# MainBoard_ETH_RASP.net
KiCad netlist of a schematic drawn in Altium Designer
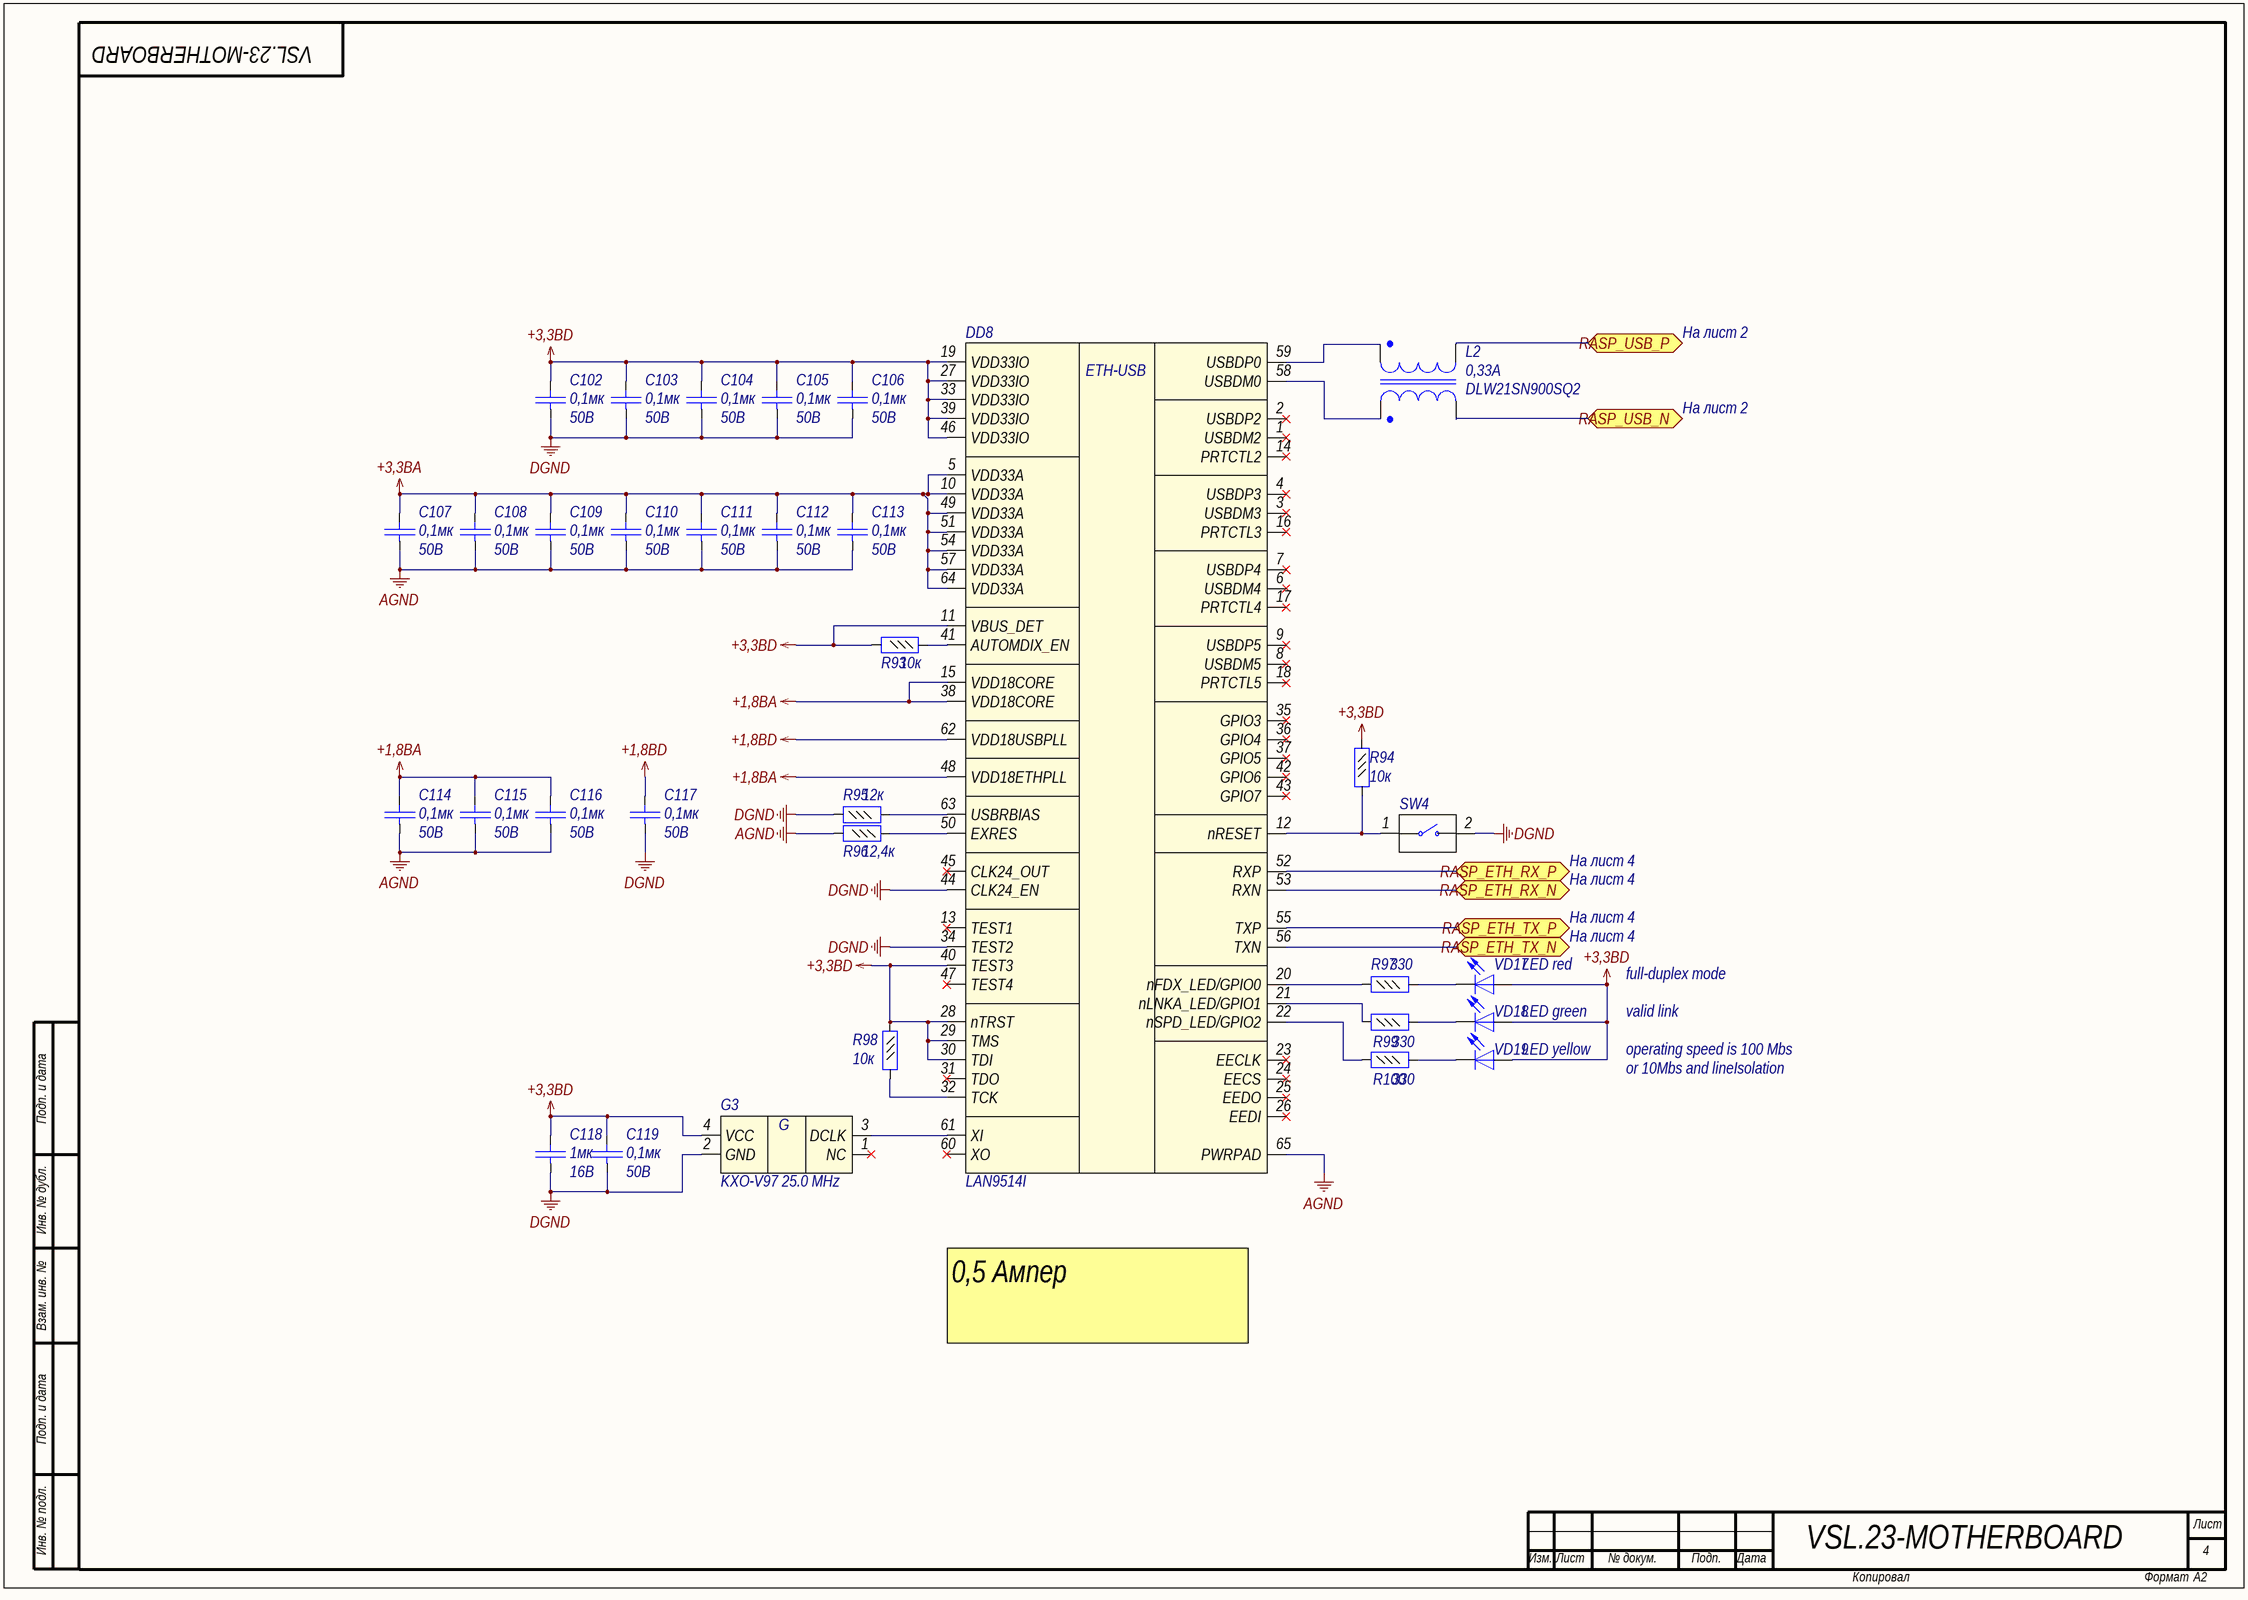
[diagram p0: MainBoard_ETH_RASP.SchDoc]

(export (version "E")
  (design (tool "Eeschema 10.0.6"))
  (components
    (comp (ref "C102")
      (value "0,1мк")
      (footprint "C0402")
      (description "Конденсатор")
      (fields
        (field (name "VOLTAGE") "50В")
        (field (name "PART NUMBER") "GRM155R71H104KE14D ")
        (field (name "Comment") "Capacitor")
      )
      (libsource (lib "MOP44") (part "Capacitor"))
    )
    (comp (ref "C103")
      (value "0,1мк")
      (footprint "C0402")
      (description "Конденсатор")
      (fields
        (field (name "VOLTAGE") "50В")
        (field (name "PART NUMBER") "GRM155R71H104KE14D ")
        (field (name "Comment") "Capacitor")
      )
      (libsource (lib "MOP44") (part "Capacitor"))
    )
    (comp (ref "C104")
      (value "0,1мк")
      (footprint "C0402")
      (description "Конденсатор")
      (fields
        (field (name "VOLTAGE") "50В")
        (field (name "PART NUMBER") "GRM155R71H104KE14D ")
        (field (name "Comment") "Capacitor")
      )
      (libsource (lib "MOP44") (part "Capacitor"))
    )
    (comp (ref "C105")
      (value "0,1мк")
      (footprint "C0402")
      (description "Конденсатор")
      (fields
        (field (name "VOLTAGE") "50В")
        (field (name "PART NUMBER") "GRM155R71H104KE14D ")
        (field (name "Comment") "Capacitor")
      )
      (libsource (lib "MOP44") (part "Capacitor"))
    )
    (comp (ref "C106")
      (value "0,1мк")
      (footprint "C0402")
      (description "Конденсатор")
      (fields
        (field (name "VOLTAGE") "50В")
        (field (name "PART NUMBER") "GRM155R71H104KE14D ")
        (field (name "Comment") "Capacitor")
      )
      (libsource (lib "MOP44") (part "Capacitor"))
    )
    (comp (ref "C107")
      (value "0,1мк")
      (footprint "C0402")
      (description "Конденсатор")
      (fields
        (field (name "VOLTAGE") "50В")
        (field (name "PART NUMBER") "GRM155R71H104KE14D ")
        (field (name "Comment") "Capacitor")
      )
      (libsource (lib "MOP44") (part "Capacitor"))
    )
    (comp (ref "C108")
      (value "0,1мк")
      (footprint "C0402")
      (description "Конденсатор")
      (fields
        (field (name "VOLTAGE") "50В")
        (field (name "PART NUMBER") "GRM155R71H104KE14D ")
        (field (name "Comment") "Capacitor")
      )
      (libsource (lib "MOP44") (part "Capacitor"))
    )
    (comp (ref "C109")
      (value "0,1мк")
      (footprint "C0402")
      (description "Конденсатор")
      (fields
        (field (name "VOLTAGE") "50В")
        (field (name "PART NUMBER") "GRM155R71H104KE14D ")
        (field (name "Comment") "Capacitor")
      )
      (libsource (lib "MOP44") (part "Capacitor"))
    )
    (comp (ref "C110")
      (value "0,1мк")
      (footprint "C0402")
      (description "Конденсатор")
      (fields
        (field (name "VOLTAGE") "50В")
        (field (name "PART NUMBER") "GRM155R71H104KE14D ")
        (field (name "Comment") "Capacitor")
      )
      (libsource (lib "MOP44") (part "Capacitor"))
    )
    (comp (ref "C111")
      (value "0,1мк")
      (footprint "C0402")
      (description "Конденсатор")
      (fields
        (field (name "VOLTAGE") "50В")
        (field (name "PART NUMBER") "GRM155R71H104KE14D ")
        (field (name "Comment") "Capacitor")
      )
      (libsource (lib "MOP44") (part "Capacitor"))
    )
    (comp (ref "C112")
      (value "0,1мк")
      (footprint "C0402")
      (description "Конденсатор")
      (fields
        (field (name "VOLTAGE") "50В")
        (field (name "PART NUMBER") "GRM155R71H104KE14D ")
        (field (name "Comment") "Capacitor")
      )
      (libsource (lib "MOP44") (part "Capacitor"))
    )
    (comp (ref "C113")
      (value "0,1мк")
      (footprint "C0402")
      (description "Конденсатор")
      (fields
        (field (name "VOLTAGE") "50В")
        (field (name "PART NUMBER") "GRM155R71H104KE14D ")
        (field (name "Comment") "Capacitor")
      )
      (libsource (lib "MOP44") (part "Capacitor"))
    )
    (comp (ref "C114")
      (value "0,1мк")
      (footprint "C0402")
      (description "Конденсатор")
      (fields
        (field (name "VOLTAGE") "50В")
        (field (name "PART NUMBER") "GRM155R71H104KE14D ")
        (field (name "Comment") "Capacitor")
      )
      (libsource (lib "MOP44") (part "Capacitor"))
    )
    (comp (ref "C115")
      (value "0,1мк")
      (footprint "C0402")
      (description "Конденсатор")
      (fields
        (field (name "VOLTAGE") "50В")
        (field (name "PART NUMBER") "GRM155R71H104KE14D ")
        (field (name "Comment") "Capacitor")
      )
      (libsource (lib "MOP44") (part "Capacitor"))
    )
    (comp (ref "C116")
      (value "0,1мк")
      (footprint "C0402")
      (description "Конденсатор")
      (fields
        (field (name "VOLTAGE") "50В")
        (field (name "PART NUMBER") "GRM155R71H104KE14D ")
        (field (name "Comment") "Capacitor")
      )
      (libsource (lib "MOP44") (part "Capacitor"))
    )
    (comp (ref "C117")
      (value "0,1мк")
      (footprint "C0402")
      (description "Конденсатор")
      (fields
        (field (name "VOLTAGE") "50В")
        (field (name "PART NUMBER") "GRM155R71H104KE14D ")
        (field (name "Comment") "Capacitor")
      )
      (libsource (lib "MOP44") (part "Capacitor"))
    )
    (comp (ref "C118")
      (value "1мк")
      (footprint "C0603")
      (description "Конденсатор")
      (fields
        (field (name "VOLTAGE") "16B")
        (field (name "PART NUMBER") "GRM188R71C105KA12D**")
        (field (name "Comment") "Capacitor")
      )
      (libsource (lib "MOP44") (part "Capacitor"))
    )
    (comp (ref "C119")
      (value "0,1мк")
      (footprint "C0402")
      (description "Конденсатор")
      (fields
        (field (name "VOLTAGE") "50В")
        (field (name "PART NUMBER") "GRM155R71H104KE14D ")
        (field (name "Comment") "Capacitor")
      )
      (libsource (lib "MOP44") (part "Capacitor"))
    )
    (comp (ref "DD8")
      (value "~")
      (footprint "QFN64")
      (description "USB 2.0 Hub and 10/100 Ethernet Controller")
      (fields (field (name "PART NUMBER") "LAN9514I"))
      (libsource (lib "MOP44") (part "LAN9514I"))
    )
    (comp (ref "G3")
      (value "KXO")
      (footprint "QSMD7x5.2x1.8")
      (description "Кварц. генер. 32.768 МГц (HCMOS/TTL)")
      (fields (field (name "PART NUMBER") "KXO-V97 25.0 MHz"))
      (libsource (lib "MOP44") (part "KXO"))
    )
    (comp (ref "L2")
      (value "Dual-Winding Inductor")
      (footprint "CHOKE0805")
      (description "Синфазный дроссель")
      (fields (field (name "RATED CURRENT") "0,33A") (field (name "PART NUMBER") "DLW21SN900SQ2"))
      (libsource (lib "MOP44") (part "Dual-Winding Inductor"))
    )
    (comp (ref "R93")
      (value "10к")
      (footprint "R0402")
      (description "Резистор")
      (fields (field (name "PART NUMBER") "RC0402FR-0710KL") (field (name "POWER") "0,062Вт"))
      (libsource (lib "MOP44") (part "Resistor_0,062Вт"))
    )
    (comp (ref "R94")
      (value "10к")
      (footprint "R0402")
      (description "Резистор")
      (fields (field (name "PART NUMBER") "RC0402FR-0710KL") (field (name "POWER") "0,062Вт"))
      (libsource (lib "") (part "Resistor_0,062Вт_2"))
    )
    (comp (ref "R95")
      (value "12к")
      (footprint "R0402")
      (description "Резистор")
      (fields (field (name "PART NUMBER") "RC0402FR-0712KL") (field (name "POWER") "0,062Вт"))
      (libsource (lib "") (part "Resistor_0,062Вт_1"))
    )
    (comp (ref "R96")
      (value "12,4к")
      (footprint "R0402")
      (description "Резистор")
      (fields (field (name "PART NUMBER") "RC0402FR-0712K4L") (field (name "POWER") "0,062Вт"))
      (libsource (lib "MOP44") (part "Resistor_0,062Вт"))
    )
    (comp (ref "R97")
      (value "330")
      (footprint "R0402")
      (description "Резистор")
      (fields (field (name "PART NUMBER") "RC0402FR-07330RL") (field (name "POWER") "0,062Вт"))
      (libsource (lib "") (part "Resistor_0,062Вт_1"))
    )
    (comp (ref "R98")
      (value "10к")
      (footprint "R0402")
      (description "Резистор")
      (fields (field (name "PART NUMBER") "RC0402FR-0710KL") (field (name "POWER") "0,062Вт"))
      (libsource (lib "") (part "Resistor_0,062Вт_2"))
    )
    (comp (ref "R99")
      (value "330")
      (footprint "R0402")
      (description "Резистор")
      (fields (field (name "PART NUMBER") "RC0402FR-07330RL") (field (name "POWER") "0,062Вт"))
      (libsource (lib "") (part "Resistor_0,062Вт_1"))
    )
    (comp (ref "R100")
      (value "330")
      (footprint "R0402")
      (description "Резистор")
      (fields (field (name "PART NUMBER") "RC0402FR-07330RL") (field (name "POWER") "0,062Вт"))
      (libsource (lib "") (part "Resistor_0,062Вт_1"))
    )
    (comp (ref "SW4")
      (value "DS1040-01")
      (footprint "JUMPER_2.54")
      (description "DIP переключатель")
      (libsource (lib "MOP44") (part "DS1040-01"))
    )
    (comp (ref "VD17")
      (value "LED")
      (footprint "L_0402_RED")
      (description "Светодиод")
      (fields (field (name "PART NAME") "LED red") (field (name "PART NUMBER") "KPHHS-1005SURCK"))
      (libsource (lib "MOP44") (part "LED"))
    )
    (comp (ref "VD18")
      (value "LED")
      (footprint "L_0402_GREEN")
      (description "Светодиод")
      (fields (field (name "PART NAME") "LED green") (field (name "PART NUMBER") "KPHHS-1005MGCK "))
      (libsource (lib "MOP44") (part "LED"))
    )
    (comp (ref "VD19")
      (value "LED")
      (footprint "L_0402_YELLOW")
      (description "Светодиод")
      (fields (field (name "PART NAME") "LED yellow") (field (name "PART NUMBER") "KPHHS-1005SYCK"))
      (libsource (lib "MOP44") (part "LED"))
    )
  )
  (nets
    (net (code "1") (name "+1,8BA") (class "Default")
      (node (ref "C114") (pin "2") (pinfunction "2_2") (pintype "passive"))
      (node (ref "C115") (pin "2") (pinfunction "2_2") (pintype "passive"))
      (node (ref "C116") (pin "2") (pinfunction "2_2") (pintype "passive"))
      (node (ref "DD8") (pin "15") (pinfunction "VDD18CORE_15") (pintype "power_in"))
      (node (ref "DD8") (pin "38") (pinfunction "VDD18CORE_38") (pintype "power_in"))
      (node (ref "DD8") (pin "48") (pinfunction "VDD18ETHPLL_48") (pintype "power_in"))
    )
    (net (code "2") (name "+1,8BD") (class "Default")
      (node (ref "C117") (pin "2") (pinfunction "2_2") (pintype "passive"))
      (node (ref "DD8") (pin "62") (pinfunction "VDD18USBPLL_62") (pintype "power_in"))
    )
    (net (code "3") (name "+3,3BA") (class "Default")
      (node (ref "C107") (pin "2") (pinfunction "2_2") (pintype "passive"))
      (node (ref "C108") (pin "2") (pinfunction "2_2") (pintype "passive"))
      (node (ref "C109") (pin "2") (pinfunction "2_2") (pintype "passive"))
      (node (ref "C110") (pin "2") (pinfunction "2_2") (pintype "passive"))
      (node (ref "C111") (pin "2") (pinfunction "2_2") (pintype "passive"))
      (node (ref "C112") (pin "2") (pinfunction "2_2") (pintype "passive"))
      (node (ref "C113") (pin "2") (pinfunction "2_2") (pintype "passive"))
      (node (ref "DD8") (pin "10") (pinfunction "VDD33A_10") (pintype "power_in"))
      (node (ref "DD8") (pin "49") (pinfunction "VDD33A_49") (pintype "power_in"))
      (node (ref "DD8") (pin "5") (pinfunction "VDD33A_5") (pintype "power_in"))
      (node (ref "DD8") (pin "51") (pinfunction "VDD33A_51") (pintype "power_in"))
      (node (ref "DD8") (pin "54") (pinfunction "VDD33A_54") (pintype "power_in"))
      (node (ref "DD8") (pin "57") (pinfunction "VDD33A_57") (pintype "power_in"))
      (node (ref "DD8") (pin "64") (pinfunction "VDD33A_64") (pintype "power_in"))
    )
    (net (code "4") (name "+3,3BD") (class "Default")
      (node (ref "C102") (pin "2") (pinfunction "2_2") (pintype "passive"))
      (node (ref "C103") (pin "2") (pinfunction "2_2") (pintype "passive"))
      (node (ref "C104") (pin "2") (pinfunction "2_2") (pintype "passive"))
      (node (ref "C105") (pin "2") (pinfunction "2_2") (pintype "passive"))
      (node (ref "C106") (pin "2") (pinfunction "2_2") (pintype "passive"))
      (node (ref "C118") (pin "2") (pinfunction "2_2") (pintype "passive"))
      (node (ref "C119") (pin "2") (pinfunction "2_2") (pintype "passive"))
      (node (ref "DD8") (pin "11") (pinfunction "VBUS_DET_11") (pintype "power_in"))
      (node (ref "DD8") (pin "19") (pinfunction "VDD33IO_19") (pintype "power_in"))
      (node (ref "DD8") (pin "27") (pinfunction "VDD33IO_27") (pintype "power_in"))
      (node (ref "DD8") (pin "28") (pinfunction "nTRST_28") (pintype "power_in"))
      (node (ref "DD8") (pin "29") (pinfunction "TMS_29") (pintype "power_in"))
      (node (ref "DD8") (pin "30") (pinfunction "TDI_30") (pintype "power_in"))
      (node (ref "DD8") (pin "33") (pinfunction "VDD33IO_33") (pintype "power_in"))
      (node (ref "DD8") (pin "39") (pinfunction "VDD33IO_39") (pintype "power_in"))
      (node (ref "DD8") (pin "40") (pinfunction "TEST3_40") (pintype "power_in"))
      (node (ref "DD8") (pin "46") (pinfunction "VDD33IO_46") (pintype "power_in"))
      (node (ref "G3") (pin "4") (pinfunction "VCC_4") (pintype "power_in"))
      (node (ref "R93") (pin "2") (pinfunction "2_2") (pintype "passive"))
      (node (ref "R94") (pin "1") (pinfunction "1_1") (pintype "passive"))
      (node (ref "R98") (pin "1") (pinfunction "1_1") (pintype "passive"))
      (node (ref "VD17") (pin "2") (pinfunction "A_2") (pintype "passive"))
      (node (ref "VD18") (pin "2") (pinfunction "A_2") (pintype "passive"))
      (node (ref "VD19") (pin "2") (pinfunction "A_2") (pintype "passive"))
    )
    (net (code "5") (name "/RASP_ETH_RX_N") (class "Default")
      (node (ref "DD8") (pin "53") (pinfunction "RXN_53") (pintype "power_in"))
    )
    (net (code "6") (name "/RASP_ETH_RX_P") (class "Default")
      (node (ref "DD8") (pin "52") (pinfunction "RXP_52") (pintype "power_in"))
    )
    (net (code "7") (name "/RASP_ETH_TX_N") (class "Default")
      (node (ref "DD8") (pin "56") (pinfunction "TXN_56") (pintype "power_in"))
    )
    (net (code "8") (name "/RASP_ETH_TX_P") (class "Default")
      (node (ref "DD8") (pin "55") (pinfunction "TXP_55") (pintype "power_in"))
    )
    (net (code "9") (name "/RASP_USB_N") (class "Default") (node (ref "L2") (pin "4") (pintype "passive")))
    (net (code "10") (name "/RASP_USB_P") (class "Default") (node (ref "L2") (pin "3") (pintype "passive")))
    (net (code "11") (name "AGND") (class "Default")
      (node (ref "C107") (pin "1") (pinfunction "1_1") (pintype "passive"))
      (node (ref "C108") (pin "1") (pinfunction "1_1") (pintype "passive"))
      (node (ref "C109") (pin "1") (pinfunction "1_1") (pintype "passive"))
      (node (ref "C110") (pin "1") (pinfunction "1_1") (pintype "passive"))
      (node (ref "C111") (pin "1") (pinfunction "1_1") (pintype "passive"))
      (node (ref "C112") (pin "1") (pinfunction "1_1") (pintype "passive"))
      (node (ref "C113") (pin "1") (pinfunction "1_1") (pintype "passive"))
      (node (ref "C114") (pin "1") (pinfunction "1_1") (pintype "passive"))
      (node (ref "C115") (pin "1") (pinfunction "1_1") (pintype "passive"))
      (node (ref "C116") (pin "1") (pinfunction "1_1") (pintype "passive"))
      (node (ref "DD8") (pin "65") (pinfunction "PWRPAD_65") (pintype "power_in"))
      (node (ref "R96") (pin "2") (pinfunction "2_2") (pintype "passive"))
    )
    (net (code "12") (name "DGND") (class "Default")
      (node (ref "C102") (pin "1") (pinfunction "1_1") (pintype "passive"))
      (node (ref "C103") (pin "1") (pinfunction "1_1") (pintype "passive"))
      (node (ref "C104") (pin "1") (pinfunction "1_1") (pintype "passive"))
      (node (ref "C105") (pin "1") (pinfunction "1_1") (pintype "passive"))
      (node (ref "C106") (pin "1") (pinfunction "1_1") (pintype "passive"))
      (node (ref "C117") (pin "1") (pinfunction "1_1") (pintype "passive"))
      (node (ref "C118") (pin "1") (pinfunction "1_1") (pintype "passive"))
      (node (ref "C119") (pin "1") (pinfunction "1_1") (pintype "passive"))
      (node (ref "DD8") (pin "34") (pinfunction "TEST2_34") (pintype "power_in"))
      (node (ref "DD8") (pin "44") (pinfunction "CLK24_EN_44") (pintype "power_in"))
      (node (ref "G3") (pin "2") (pinfunction "GND_2") (pintype "power_in"))
      (node (ref "R95") (pin "1") (pinfunction "1_1") (pintype "passive"))
      (node (ref "SW4") (pin "2") (pintype "passive"))
    )
    (net (code "13") (name "Net-(DD8-AUTOMDIX_EN)") (class "Default")
      (node (ref "DD8") (pin "41") (pinfunction "AUTOMDIX_EN_41") (pintype "power_in"))
      (node (ref "R93") (pin "1") (pinfunction "1_1") (pintype "passive"))
    )
    (net (code "14") (name "Net-(DD8-EXRES)") (class "Default")
      (node (ref "DD8") (pin "50") (pinfunction "EXRES_50") (pintype "power_in"))
      (node (ref "R96") (pin "1") (pinfunction "1_1") (pintype "passive"))
    )
    (net (code "15") (name "Net-(DD8-TCK)") (class "Default")
      (node (ref "DD8") (pin "32") (pinfunction "TCK_32") (pintype "power_in"))
      (node (ref "R98") (pin "2") (pinfunction "2_2") (pintype "passive"))
    )
    (net (code "16") (name "Net-(DD8-USBDM0)") (class "Default")
      (node (ref "DD8") (pin "58") (pinfunction "USBDM0_58") (pintype "power_in"))
      (node (ref "L2") (pin "2") (pintype "passive"))
    )
    (net (code "17") (name "Net-(DD8-USBDP0)") (class "Default")
      (node (ref "DD8") (pin "59") (pinfunction "USBDP0_59") (pintype "power_in"))
      (node (ref "L2") (pin "1") (pintype "passive"))
    )
    (net (code "18") (name "Net-(DD8-USBRBIAS)") (class "Default")
      (node (ref "DD8") (pin "63") (pinfunction "USBRBIAS_63") (pintype "power_in"))
      (node (ref "R95") (pin "2") (pinfunction "2_2") (pintype "passive"))
    )
    (net (code "19") (name "Net-(DD8-XI)") (class "Default")
      (node (ref "DD8") (pin "61") (pinfunction "XI_61") (pintype "power_in"))
      (node (ref "G3") (pin "3") (pinfunction "DCLK_3") (pintype "power_in"))
    )
    (net (code "20") (name "Net-(DD8-nFDX_LED{slash}GPIO0)") (class "Default")
      (node (ref "DD8") (pin "20") (pinfunction "nFDX_LED/GPIO0_20") (pintype "power_in"))
      (node (ref "R97") (pin "1") (pinfunction "1_1") (pintype "passive"))
    )
    (net (code "21") (name "Net-(DD8-nLNKA_LED{slash}GPIO1)") (class "Default")
      (node (ref "DD8") (pin "21") (pinfunction "nLNKA_LED/GPIO1_21") (pintype "power_in"))
      (node (ref "R99") (pin "1") (pinfunction "1_1") (pintype "passive"))
    )
    (net (code "22") (name "Net-(DD8-nRESET)") (class "Default")
      (node (ref "DD8") (pin "12") (pinfunction "nRESET_12") (pintype "power_in"))
      (node (ref "R94") (pin "2") (pinfunction "2_2") (pintype "passive"))
      (node (ref "SW4") (pin "1") (pintype "passive"))
    )
    (net (code "23") (name "Net-(DD8-nSPD_LED{slash}GPIO2)") (class "Default")
      (node (ref "DD8") (pin "22") (pinfunction "nSPD_LED/GPIO2_22") (pintype "power_in"))
      (node (ref "R100") (pin "1") (pinfunction "1_1") (pintype "passive"))
    )
    (net (code "24") (name "Net-(VD17-K)") (class "Default")
      (node (ref "R97") (pin "2") (pinfunction "2_2") (pintype "passive"))
      (node (ref "VD17") (pin "1") (pinfunction "K_1") (pintype "passive"))
    )
    (net (code "25") (name "Net-(VD18-K)") (class "Default")
      (node (ref "R99") (pin "2") (pinfunction "2_2") (pintype "passive"))
      (node (ref "VD18") (pin "1") (pinfunction "K_1") (pintype "passive"))
    )
    (net (code "26") (name "Net-(VD19-K)") (class "Default")
      (node (ref "R100") (pin "2") (pinfunction "2_2") (pintype "passive"))
      (node (ref "VD19") (pin "1") (pinfunction "K_1") (pintype "passive"))
    )
    (net (code "27") (name "unconnected-(DD8-CLK24_OUT-Pad45)") (class "Default")
      (node (ref "DD8") (pin "45") (pinfunction "CLK24_OUT_45") (pintype "power_in+no_connect"))
    )
    (net (code "28") (name "unconnected-(DD8-EECLK-Pad23)") (class "Default")
      (node (ref "DD8") (pin "23") (pinfunction "EECLK_23") (pintype "power_in+no_connect"))
    )
    (net (code "29") (name "unconnected-(DD8-EECS-Pad24)") (class "Default")
      (node (ref "DD8") (pin "24") (pinfunction "EECS_24") (pintype "power_in+no_connect"))
    )
    (net (code "30") (name "unconnected-(DD8-EEDI-Pad26)") (class "Default")
      (node (ref "DD8") (pin "26") (pinfunction "EEDI_26") (pintype "power_in+no_connect"))
    )
    (net (code "31") (name "unconnected-(DD8-EEDO-Pad25)") (class "Default")
      (node (ref "DD8") (pin "25") (pinfunction "EEDO_25") (pintype "power_in+no_connect"))
    )
    (net (code "32") (name "unconnected-(DD8-GPIO3-Pad35)") (class "Default")
      (node (ref "DD8") (pin "35") (pinfunction "GPIO3_35") (pintype "power_in+no_connect"))
    )
    (net (code "33") (name "unconnected-(DD8-GPIO4-Pad36)") (class "Default")
      (node (ref "DD8") (pin "36") (pinfunction "GPIO4_36") (pintype "power_in+no_connect"))
    )
    (net (code "34") (name "unconnected-(DD8-GPIO5-Pad37)") (class "Default")
      (node (ref "DD8") (pin "37") (pinfunction "GPIO5_37") (pintype "power_in+no_connect"))
    )
    (net (code "35") (name "unconnected-(DD8-GPIO6-Pad42)") (class "Default")
      (node (ref "DD8") (pin "42") (pinfunction "GPIO6_42") (pintype "power_in+no_connect"))
    )
    (net (code "36") (name "unconnected-(DD8-GPIO7-Pad43)") (class "Default")
      (node (ref "DD8") (pin "43") (pinfunction "GPIO7_43") (pintype "power_in+no_connect"))
    )
    (net (code "37") (name "unconnected-(DD8-PRTCTL2-Pad14)") (class "Default")
      (node (ref "DD8") (pin "14") (pinfunction "PRTCTL2_14") (pintype "power_in+no_connect"))
    )
    (net (code "38") (name "unconnected-(DD8-PRTCTL3-Pad16)") (class "Default")
      (node (ref "DD8") (pin "16") (pinfunction "PRTCTL3_16") (pintype "power_in+no_connect"))
    )
    (net (code "39") (name "unconnected-(DD8-PRTCTL4-Pad17)") (class "Default")
      (node (ref "DD8") (pin "17") (pinfunction "PRTCTL4_17") (pintype "power_in+no_connect"))
    )
    (net (code "40") (name "unconnected-(DD8-PRTCTL5-Pad18)") (class "Default")
      (node (ref "DD8") (pin "18") (pinfunction "PRTCTL5_18") (pintype "power_in+no_connect"))
    )
    (net (code "41") (name "unconnected-(DD8-TDO-Pad31)") (class "Default")
      (node (ref "DD8") (pin "31") (pinfunction "TDO_31") (pintype "power_in+no_connect"))
    )
    (net (code "42") (name "unconnected-(DD8-TEST1-Pad13)") (class "Default")
      (node (ref "DD8") (pin "13") (pinfunction "TEST1_13") (pintype "power_in+no_connect"))
    )
    (net (code "43") (name "unconnected-(DD8-TEST4-Pad47)") (class "Default")
      (node (ref "DD8") (pin "47") (pinfunction "TEST4_47") (pintype "power_in+no_connect"))
    )
    (net (code "44") (name "unconnected-(DD8-USBDM2-Pad1)") (class "Default")
      (node (ref "DD8") (pin "1") (pinfunction "USBDM2_1") (pintype "power_in+no_connect"))
    )
    (net (code "45") (name "unconnected-(DD8-USBDM3-Pad3)") (class "Default")
      (node (ref "DD8") (pin "3") (pinfunction "USBDM3_3") (pintype "power_in+no_connect"))
    )
    (net (code "46") (name "unconnected-(DD8-USBDM4-Pad6)") (class "Default")
      (node (ref "DD8") (pin "6") (pinfunction "USBDM4_6") (pintype "power_in+no_connect"))
    )
    (net (code "47") (name "unconnected-(DD8-USBDM5-Pad8)") (class "Default")
      (node (ref "DD8") (pin "8") (pinfunction "USBDM5_8") (pintype "power_in+no_connect"))
    )
    (net (code "48") (name "unconnected-(DD8-USBDP2-Pad2)") (class "Default")
      (node (ref "DD8") (pin "2") (pinfunction "USBDP2_2") (pintype "power_in+no_connect"))
    )
    (net (code "49") (name "unconnected-(DD8-USBDP3-Pad4)") (class "Default")
      (node (ref "DD8") (pin "4") (pinfunction "USBDP3_4") (pintype "power_in+no_connect"))
    )
    (net (code "50") (name "unconnected-(DD8-USBDP4-Pad7)") (class "Default")
      (node (ref "DD8") (pin "7") (pinfunction "USBDP4_7") (pintype "power_in+no_connect"))
    )
    (net (code "51") (name "unconnected-(DD8-USBDP5-Pad9)") (class "Default")
      (node (ref "DD8") (pin "9") (pinfunction "USBDP5_9") (pintype "power_in+no_connect"))
    )
    (net (code "52") (name "unconnected-(DD8-XO-Pad60)") (class "Default")
      (node (ref "DD8") (pin "60") (pinfunction "XO_60") (pintype "power_in+no_connect"))
    )
    (net (code "53") (name "unconnected-(G3-NC-Pad1)") (class "Default")
      (node (ref "G3") (pin "1") (pinfunction "NC_1") (pintype "power_in+no_connect"))
    )
  )
)
